# PolluxSensorSound.net
KiCad netlist of a schematic drawn in EAGLE
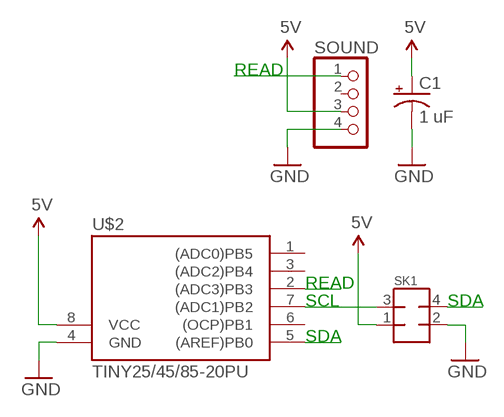
[diagram p0: schematic, sheet 1]

(export (version "E")
  (design (tool "Eeschema 10.0.6"))
  (components
    (comp (ref "C1")
      (value "1 uF")
      (footprint "eagle-import:CPOL-RADIAL-10UF-25V")
      (libsource (lib "eagle-import") (part "CAP_POLPTH2"))
    )
    (comp (ref "SK1")
      (value "MMATCH-8-PTH")
      (footprint "eagle-import:AMP-215079-8")
      (libsource (lib "eagle-import") (part "MMATCH-8-PTH"))
    )
    (comp (ref "SOUND")
      (value "PINHD-1X04_2.00")
      (footprint "eagle-import:1X04M")
      (libsource (lib "eagle-import") (part "PINHD-1X04_2.00"))
    )
    (comp (ref "U$2")
      (value "TINY25/45/85-20PU")
      (footprint "eagle-import:DIL08")
      (libsource (lib "eagle-import") (part "TINY25/45/85-20PU"))
    )
  )
  (nets
    (net (code "1") (name "/READ") (class "Default")
      (node (ref "SOUND") (pin "1") (pinfunction "1_1") (pintype "passive"))
      (node (ref "U$2") (pin "2") (pinfunction "(ADC3)PB3_2") (pintype "bidirectional"))
    )
    (net (code "2") (name "/SDA") (class "Default")
      (node (ref "SK1") (pin "4") (pinfunction "4_4") (pintype "bidirectional"))
      (node (ref "U$2") (pin "5") (pinfunction "(AREF)PB0_5") (pintype "bidirectional"))
    )
    (net (code "3") (name "5V") (class "Default")
      (node (ref "C1") (pin "1") (pinfunction "+_1") (pintype "passive"))
      (node (ref "SK1") (pin "1") (pinfunction "1_1") (pintype "bidirectional"))
      (node (ref "SOUND") (pin "3") (pinfunction "3_3") (pintype "passive"))
      (node (ref "U$2") (pin "8") (pinfunction "VCC_8") (pintype "power_in"))
    )
    (net (code "4") (name "GND") (class "Default")
      (node (ref "C1") (pin "2") (pinfunction "-_2") (pintype "passive"))
      (node (ref "SK1") (pin "2") (pinfunction "2_2") (pintype "bidirectional"))
      (node (ref "SOUND") (pin "4") (pinfunction "4_4") (pintype "passive"))
      (node (ref "U$2") (pin "4") (pinfunction "GND_4") (pintype "power_in"))
    )
    (net (code "5") (name "Net-(U$2-(ADC1)PB2)") (class "Default")
      (node (ref "SK1") (pin "3") (pinfunction "3_3") (pintype "bidirectional"))
      (node (ref "U$2") (pin "7") (pinfunction "(ADC1)PB2_7") (pintype "bidirectional"))
    )
    (net (code "6") (name "unconnected-(SOUND-Pad2)") (class "Default")
      (node (ref "SOUND") (pin "2") (pinfunction "2_2") (pintype "passive"))
    )
    (net (code "7") (name "unconnected-(U$2-(ADC0)PB5-Pad1)") (class "Default")
      (node (ref "U$2") (pin "1") (pinfunction "(ADC0)PB5_1") (pintype "bidirectional"))
    )
    (net (code "8") (name "unconnected-(U$2-(ADC2)PB4-Pad3)") (class "Default")
      (node (ref "U$2") (pin "3") (pinfunction "(ADC2)PB4_3") (pintype "bidirectional"))
    )
    (net (code "9") (name "unconnected-(U$2-(OCP)PB1-Pad6)") (class "Default")
      (node (ref "U$2") (pin "6") (pinfunction "(OCP)PB1_6") (pintype "bidirectional"))
    )
  )
)
